# modulator_r1.net
KiCad netlist of a schematic drawn in EAGLE
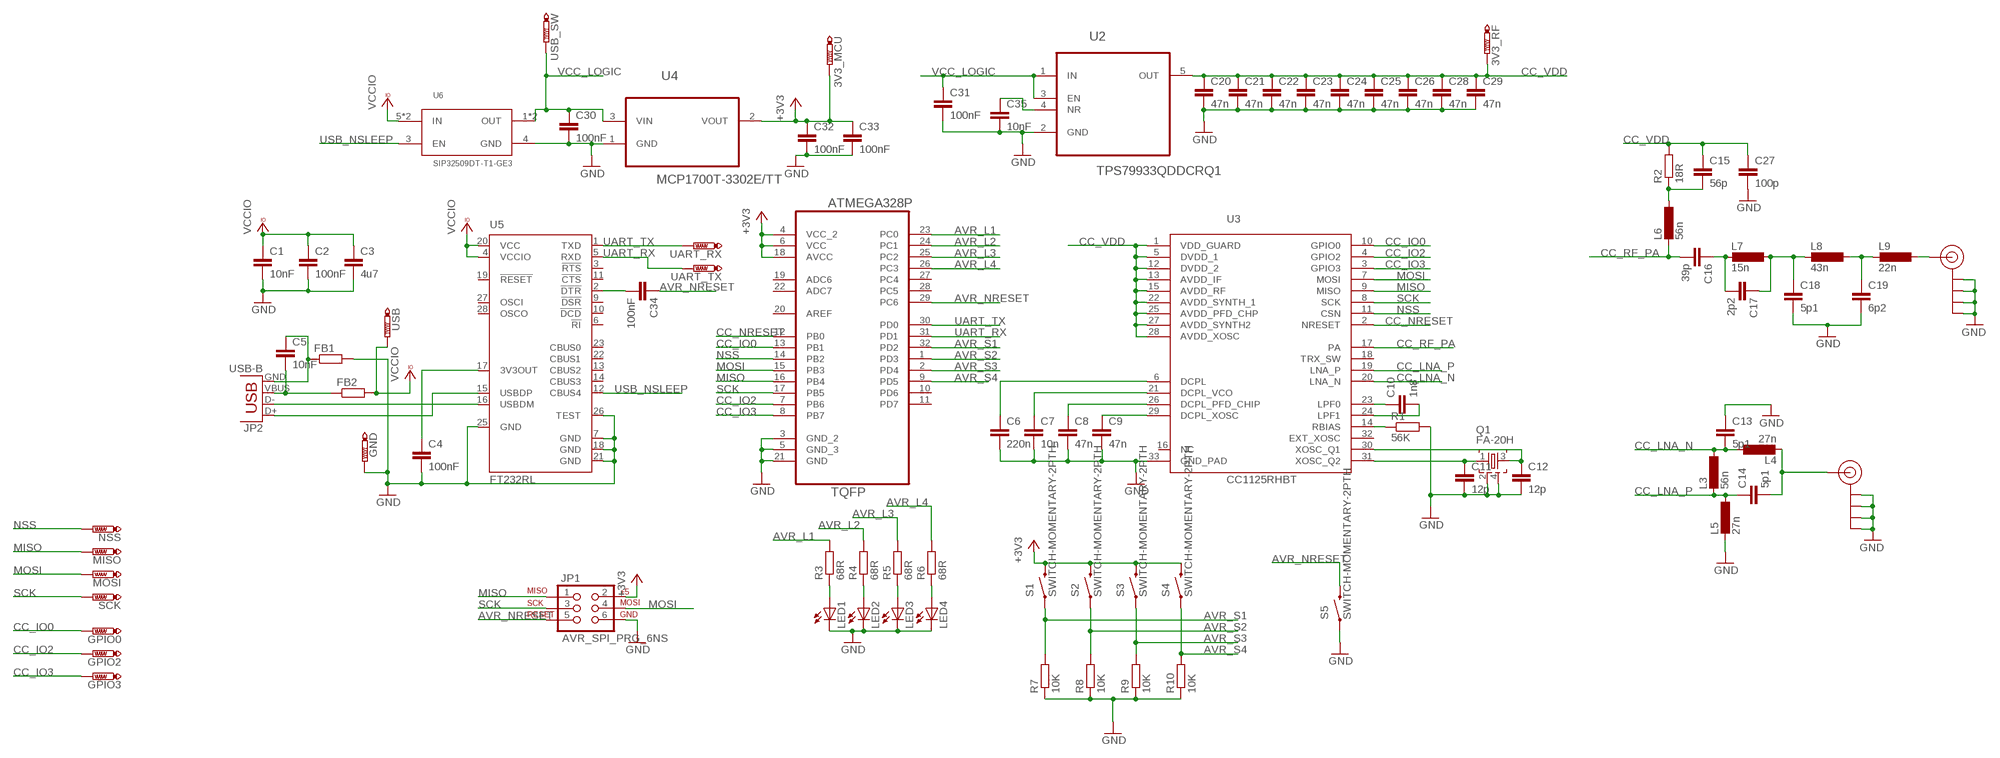
[diagram p0: schematic, sheet 1]

(export (version "E")
  (design (tool "Eeschema 10.0.6"))
  (components
    (comp (ref "3V3_MCU")
      (value "PTR1B2,54")
      (footprint "eagle-import:B2,54")
      (libsource (lib "eagle-import") (part "PTR1B2,54"))
    )
    (comp (ref "3V3_RF")
      (value "PTR1B2,54")
      (footprint "eagle-import:B2,54")
      (libsource (lib "eagle-import") (part "PTR1B2,54"))
    )
    (comp (ref "C1")
      (value "10nF")
      (footprint "eagle-import:C0603")
      (libsource (lib "eagle-import") (part "C-EUC0603"))
    )
    (comp (ref "C2")
      (value "100nF")
      (footprint "eagle-import:C0603")
      (libsource (lib "eagle-import") (part "C-EUC0603"))
    )
    (comp (ref "C3")
      (value "4u7")
      (footprint "eagle-import:C0603")
      (libsource (lib "eagle-import") (part "C-EUC0603"))
    )
    (comp (ref "C4")
      (value "100nF")
      (footprint "eagle-import:C0603")
      (libsource (lib "eagle-import") (part "C-EUC0603"))
    )
    (comp (ref "C5")
      (value "10nF")
      (footprint "eagle-import:C0603")
      (libsource (lib "eagle-import") (part "C-EUC0603"))
    )
    (comp (ref "C6")
      (value "220n")
      (footprint "eagle-import:C0402")
      (libsource (lib "eagle-import") (part "C-EUC0402"))
    )
    (comp (ref "C7")
      (value "10n")
      (footprint "eagle-import:C0402")
      (libsource (lib "eagle-import") (part "C-EUC0402"))
    )
    (comp (ref "C8")
      (value "47n")
      (footprint "eagle-import:C0402")
      (libsource (lib "eagle-import") (part "C-EUC0402"))
    )
    (comp (ref "C9")
      (value "47n")
      (footprint "eagle-import:C0402")
      (libsource (lib "eagle-import") (part "C-EUC0402"))
    )
    (comp (ref "C10")
      (value "1n8")
      (footprint "eagle-import:C0402")
      (libsource (lib "eagle-import") (part "C-EUC0402"))
    )
    (comp (ref "C11")
      (value "12p")
      (footprint "eagle-import:C0402")
      (libsource (lib "eagle-import") (part "C-EUC0402"))
    )
    (comp (ref "C12")
      (value "12p")
      (footprint "eagle-import:C0402")
      (libsource (lib "eagle-import") (part "C-EUC0402"))
    )
    (comp (ref "C13")
      (value "5p1")
      (footprint "eagle-import:C0402")
      (libsource (lib "eagle-import") (part "C-EUC0402"))
    )
    (comp (ref "C14")
      (value "5p1")
      (footprint "eagle-import:C0402")
      (libsource (lib "eagle-import") (part "C-EUC0402"))
    )
    (comp (ref "C15")
      (value "56p")
      (footprint "eagle-import:C0402")
      (libsource (lib "eagle-import") (part "C-EUC0402"))
    )
    (comp (ref "C16")
      (value "39p")
      (footprint "eagle-import:C0402")
      (libsource (lib "eagle-import") (part "C-EUC0402"))
    )
    (comp (ref "C17")
      (value "2p2")
      (footprint "eagle-import:C0402")
      (libsource (lib "eagle-import") (part "C-EUC0402"))
    )
    (comp (ref "C18")
      (value "5p1")
      (footprint "eagle-import:C0402")
      (libsource (lib "eagle-import") (part "C-EUC0402"))
    )
    (comp (ref "C19")
      (value "6p2")
      (footprint "eagle-import:C0402")
      (libsource (lib "eagle-import") (part "C-EUC0402"))
    )
    (comp (ref "C20")
      (value "47n")
      (footprint "eagle-import:C0402")
      (libsource (lib "eagle-import") (part "C-EUC0402"))
    )
    (comp (ref "C21")
      (value "47n")
      (footprint "eagle-import:C0402")
      (libsource (lib "eagle-import") (part "C-EUC0402"))
    )
    (comp (ref "C22")
      (value "47n")
      (footprint "eagle-import:C0402")
      (libsource (lib "eagle-import") (part "C-EUC0402"))
    )
    (comp (ref "C23")
      (value "47n")
      (footprint "eagle-import:C0402")
      (libsource (lib "eagle-import") (part "C-EUC0402"))
    )
    (comp (ref "C24")
      (value "47n")
      (footprint "eagle-import:C0402")
      (libsource (lib "eagle-import") (part "C-EUC0402"))
    )
    (comp (ref "C25")
      (value "47n")
      (footprint "eagle-import:C0402")
      (libsource (lib "eagle-import") (part "C-EUC0402"))
    )
    (comp (ref "C26")
      (value "47n")
      (footprint "eagle-import:C0402")
      (libsource (lib "eagle-import") (part "C-EUC0402"))
    )
    (comp (ref "C27")
      (value "100p")
      (footprint "eagle-import:C0402")
      (libsource (lib "eagle-import") (part "C-EUC0402"))
    )
    (comp (ref "C28")
      (value "47n")
      (footprint "eagle-import:C0402")
      (libsource (lib "eagle-import") (part "C-EUC0402"))
    )
    (comp (ref "C29")
      (value "47n")
      (footprint "eagle-import:C0402")
      (libsource (lib "eagle-import") (part "C-EUC0402"))
    )
    (comp (ref "C30")
      (value "100nF")
      (footprint "eagle-import:C0603")
      (libsource (lib "eagle-import") (part "C-EUC0603"))
    )
    (comp (ref "C31")
      (value "100nF")
      (footprint "eagle-import:C0603")
      (libsource (lib "eagle-import") (part "C-EUC0603"))
    )
    (comp (ref "C32")
      (value "100nF")
      (footprint "eagle-import:C0603")
      (libsource (lib "eagle-import") (part "C-EUC0603"))
    )
    (comp (ref "C33")
      (value "100nF")
      (footprint "eagle-import:C0603")
      (libsource (lib "eagle-import") (part "C-EUC0603"))
    )
    (comp (ref "C34")
      (value "100nF")
      (footprint "eagle-import:C0603")
      (libsource (lib "eagle-import") (part "C-EUC0603"))
    )
    (comp (ref "C35")
      (value "10nF")
      (footprint "eagle-import:C0603")
      (libsource (lib "eagle-import") (part "C-EUC0603"))
    )
    (comp (ref "FB1")
      (value "R-EU_R0603")
      (footprint "eagle-import:R0603")
      (libsource (lib "eagle-import") (part "R-EU_R0603"))
    )
    (comp (ref "FB2")
      (value "R-EU_R0603")
      (footprint "eagle-import:R0603")
      (libsource (lib "eagle-import") (part "R-EU_R0603"))
    )
    (comp (ref "GND")
      (value "PTR1B2,54")
      (footprint "eagle-import:B2,54")
      (libsource (lib "eagle-import") (part "PTR1B2,54"))
    )
    (comp (ref "GPIO0")
      (value "PTR1B1,27")
      (footprint "eagle-import:B1,27")
      (libsource (lib "eagle-import") (part "PTR1B1,27"))
    )
    (comp (ref "GPIO2")
      (value "PTR1B1,27")
      (footprint "eagle-import:B1,27")
      (libsource (lib "eagle-import") (part "PTR1B1,27"))
    )
    (comp (ref "GPIO3")
      (value "PTR1B1,27")
      (footprint "eagle-import:B1,27")
      (libsource (lib "eagle-import") (part "PTR1B1,27"))
    )
    (comp (ref "J$1")
      (value "SMA_EDGE")
      (footprint "eagle-import:SMA-EDGE")
      (libsource (lib "eagle-import") (part "SMA_EDGE"))
    )
    (comp (ref "J$2")
      (value "SMA_EDGE")
      (footprint "eagle-import:SMA-EDGE")
      (libsource (lib "eagle-import") (part "SMA_EDGE"))
    )
    (comp (ref "JP1")
      (value "AVR_SPI_PRG_6NS")
      (footprint "eagle-import:2X3-NS")
      (libsource (lib "eagle-import") (part "AVR_SPI_PRG_6NS"))
    )
    (comp (ref "JP2")
      (value "USB-B")
      (footprint "eagle-import:USB-B-PTH")
      (libsource (lib "eagle-import") (part "USBPTH"))
    )
    (comp (ref "L3")
      (value "56n")
      (footprint "eagle-import:R0402")
      (libsource (lib "eagle-import") (part "L-EUL0402"))
    )
    (comp (ref "L4")
      (value "27n")
      (footprint "eagle-import:R0402")
      (libsource (lib "eagle-import") (part "L-EUL0402"))
    )
    (comp (ref "L5")
      (value "27n")
      (footprint "eagle-import:R0402")
      (libsource (lib "eagle-import") (part "L-EUL0402"))
    )
    (comp (ref "L6")
      (value "56n")
      (footprint "eagle-import:R0402")
      (libsource (lib "eagle-import") (part "L-EUL0402"))
    )
    (comp (ref "L7")
      (value "15n")
      (footprint "eagle-import:R0402")
      (libsource (lib "eagle-import") (part "L-EUL0402"))
    )
    (comp (ref "L8")
      (value "43n")
      (footprint "eagle-import:R0402")
      (libsource (lib "eagle-import") (part "L-EUL0402"))
    )
    (comp (ref "L9")
      (value "22n")
      (footprint "eagle-import:R0402")
      (libsource (lib "eagle-import") (part "L-EUL0402"))
    )
    (comp (ref "LED1")
      (value "LEDCHIPLED_1206")
      (footprint "eagle-import:CHIPLED_1206")
      (libsource (lib "eagle-import") (part "LEDCHIPLED_1206"))
    )
    (comp (ref "LED2")
      (value "LEDCHIPLED_1206")
      (footprint "eagle-import:CHIPLED_1206")
      (libsource (lib "eagle-import") (part "LEDCHIPLED_1206"))
    )
    (comp (ref "LED3")
      (value "LEDCHIPLED_1206")
      (footprint "eagle-import:CHIPLED_1206")
      (libsource (lib "eagle-import") (part "LEDCHIPLED_1206"))
    )
    (comp (ref "LED4")
      (value "LEDCHIPLED_1206")
      (footprint "eagle-import:CHIPLED_1206")
      (libsource (lib "eagle-import") (part "LEDCHIPLED_1206"))
    )
    (comp (ref "MISO")
      (value "PTR1B1,27")
      (footprint "eagle-import:B1,27")
      (libsource (lib "eagle-import") (part "PTR1B1,27"))
    )
    (comp (ref "MOSI")
      (value "PTR1B1,27")
      (footprint "eagle-import:B1,27")
      (libsource (lib "eagle-import") (part "PTR1B1,27"))
    )
    (comp (ref "NSS")
      (value "PTR1B1,27")
      (footprint "eagle-import:B1,27")
      (libsource (lib "eagle-import") (part "PTR1B1,27"))
    )
    (comp (ref "Q1")
      (value "FA-20H")
      (footprint "eagle-import:FA-20H")
      (libsource (lib "eagle-import") (part "FA-20H"))
    )
    (comp (ref "R1")
      (value "56K")
      (footprint "eagle-import:R0402")
      (libsource (lib "eagle-import") (part "R-EU_R0402"))
    )
    (comp (ref "R2")
      (value "18R")
      (footprint "eagle-import:R0402")
      (libsource (lib "eagle-import") (part "R-EU_R0402"))
    )
    (comp (ref "R3")
      (value "68R")
      (footprint "eagle-import:R0603")
      (libsource (lib "eagle-import") (part "R-EU_R0603"))
    )
    (comp (ref "R4")
      (value "68R")
      (footprint "eagle-import:R0603")
      (libsource (lib "eagle-import") (part "R-EU_R0603"))
    )
    (comp (ref "R5")
      (value "68R")
      (footprint "eagle-import:R0603")
      (libsource (lib "eagle-import") (part "R-EU_R0603"))
    )
    (comp (ref "R6")
      (value "68R")
      (footprint "eagle-import:R0603")
      (libsource (lib "eagle-import") (part "R-EU_R0603"))
    )
    (comp (ref "R7")
      (value "10K")
      (footprint "eagle-import:R0603")
      (libsource (lib "eagle-import") (part "R-EU_R0603"))
    )
    (comp (ref "R8")
      (value "10K")
      (footprint "eagle-import:R0603")
      (libsource (lib "eagle-import") (part "R-EU_R0603"))
    )
    (comp (ref "R9")
      (value "10K")
      (footprint "eagle-import:R0603")
      (libsource (lib "eagle-import") (part "R-EU_R0603"))
    )
    (comp (ref "R10")
      (value "10K")
      (footprint "eagle-import:R0603")
      (libsource (lib "eagle-import") (part "R-EU_R0603"))
    )
    (comp (ref "S1")
      (value "SWITCH-MOMENTARY-2PTH")
      (footprint "eagle-import:TACTILE-PTH")
      (libsource (lib "eagle-import") (part "SWITCH-MOMENTARY-2PTH"))
    )
    (comp (ref "S2")
      (value "SWITCH-MOMENTARY-2PTH")
      (footprint "eagle-import:TACTILE-PTH")
      (libsource (lib "eagle-import") (part "SWITCH-MOMENTARY-2PTH"))
    )
    (comp (ref "S3")
      (value "SWITCH-MOMENTARY-2PTH")
      (footprint "eagle-import:TACTILE-PTH")
      (libsource (lib "eagle-import") (part "SWITCH-MOMENTARY-2PTH"))
    )
    (comp (ref "S4")
      (value "SWITCH-MOMENTARY-2PTH")
      (footprint "eagle-import:TACTILE-PTH")
      (libsource (lib "eagle-import") (part "SWITCH-MOMENTARY-2PTH"))
    )
    (comp (ref "S5")
      (value "SWITCH-MOMENTARY-2PTH")
      (footprint "eagle-import:TACTILE-PTH")
      (libsource (lib "eagle-import") (part "SWITCH-MOMENTARY-2PTH"))
    )
    (comp (ref "SCK")
      (value "PTR1B1,27")
      (footprint "eagle-import:B1,27")
      (libsource (lib "eagle-import") (part "PTR1B1,27"))
    )
    (comp (ref "U1")
      (value "ATMEGA328P-AU")
      (footprint "eagle-import:QFP80P900X900X120-32N")
      (libsource (lib "eagle-import") (part "ATMEGA328P-AU"))
    )
    (comp (ref "U2")
      (value "TPS79933QDDCRQ1")
      (footprint "eagle-import:SOT95P280X110-5N")
      (libsource (lib "eagle-import") (part "TPS79933QDDCRQ1"))
    )
    (comp (ref "U3")
      (value "CC1125RHBT")
      (footprint "eagle-import:QFN50P500X500X100-32N")
      (libsource (lib "eagle-import") (part "CC1125RHBT"))
    )
    (comp (ref "U4")
      (value "MCP1700T-3302E/TT")
      (footprint "eagle-import:SOT95P237X112-3N")
      (libsource (lib "eagle-import") (part "MCP1700T-3302E/TT"))
    )
    (comp (ref "U5")
      (value "FT232RL")
      (footprint "eagle-import:SSOP28")
      (libsource (lib "eagle-import") (part "FT232RL"))
    )
    (comp (ref "U6")
      (value "SIP32509DT-T1-GE3")
      (footprint "eagle-import:SOT23-6")
      (libsource (lib "eagle-import") (part "SIP32509DT-T1-GE3"))
    )
    (comp (ref "UART_RX")
      (value "PTR1B1,27")
      (footprint "eagle-import:B1,27")
      (libsource (lib "eagle-import") (part "PTR1B1,27"))
    )
    (comp (ref "UART_TX")
      (value "PTR1B1,27")
      (footprint "eagle-import:B1,27")
      (libsource (lib "eagle-import") (part "PTR1B1,27"))
    )
    (comp (ref "USB")
      (value "PTR1B2,54")
      (footprint "eagle-import:B2,54")
      (libsource (lib "eagle-import") (part "PTR1B2,54"))
    )
    (comp (ref "USB_SW")
      (value "PTR1B2,54")
      (footprint "eagle-import:B2,54")
      (libsource (lib "eagle-import") (part "PTR1B2,54"))
    )
  )
  (nets
    (net (code "1") (name "+3V3") (class "Default")
      (node (ref "3V3_MCU") (pin "TP") (pinfunction "TP_TP") (pintype "input"))
      (node (ref "C32") (pin "1") (pinfunction "1_1") (pintype "passive"))
      (node (ref "C33") (pin "1") (pinfunction "1_1") (pintype "passive"))
      (node (ref "JP1") (pin "2") (pinfunction "2_2") (pintype "passive"))
      (node (ref "S1") (pin "3") (pinfunction "2_3") (pintype "passive"))
      (node (ref "S2") (pin "3") (pinfunction "2_3") (pintype "passive"))
      (node (ref "S3") (pin "3") (pinfunction "2_3") (pintype "passive"))
      (node (ref "S4") (pin "3") (pinfunction "2_3") (pintype "passive"))
      (node (ref "U1") (pin "18") (pinfunction "AVCC_18") (pintype "power_in"))
      (node (ref "U1") (pin "4") (pinfunction "VCC_2_4") (pintype "power_in"))
      (node (ref "U1") (pin "6") (pinfunction "VCC_6") (pintype "power_in"))
      (node (ref "U4") (pin "2") (pinfunction "VOUT_2") (pintype "output"))
    )
    (net (code "2") (name "/AVR_L1") (class "Default")
      (node (ref "R3") (pin "2") (pinfunction "2_2") (pintype "passive"))
      (node (ref "U1") (pin "23") (pinfunction "PC0_23") (pintype "bidirectional"))
    )
    (net (code "3") (name "/AVR_L2") (class "Default")
      (node (ref "R4") (pin "2") (pinfunction "2_2") (pintype "passive"))
      (node (ref "U1") (pin "24") (pinfunction "PC1_24") (pintype "bidirectional"))
    )
    (net (code "4") (name "/AVR_L3") (class "Default")
      (node (ref "R5") (pin "2") (pinfunction "2_2") (pintype "passive"))
      (node (ref "U1") (pin "25") (pinfunction "PC2_25") (pintype "bidirectional"))
    )
    (net (code "5") (name "/AVR_L4") (class "Default")
      (node (ref "R6") (pin "2") (pinfunction "2_2") (pintype "passive"))
      (node (ref "U1") (pin "26") (pinfunction "PC3_26") (pintype "bidirectional"))
    )
    (net (code "6") (name "/AVR_NRESET") (class "Default")
      (node (ref "C34") (pin "1") (pinfunction "1_1") (pintype "passive"))
      (node (ref "JP1") (pin "5") (pinfunction "5_5") (pintype "passive"))
      (node (ref "S5") (pin "3") (pinfunction "2_3") (pintype "passive"))
      (node (ref "U1") (pin "29") (pinfunction "PC6_29") (pintype "bidirectional"))
    )
    (net (code "7") (name "/AVR_S1") (class "Default")
      (node (ref "R7") (pin "2") (pinfunction "2_2") (pintype "passive"))
      (node (ref "S1") (pin "1") (pinfunction "1_1") (pintype "passive"))
      (node (ref "U1") (pin "32") (pinfunction "PD2_32") (pintype "bidirectional"))
    )
    (net (code "8") (name "/AVR_S2") (class "Default")
      (node (ref "R8") (pin "2") (pinfunction "2_2") (pintype "passive"))
      (node (ref "S2") (pin "1") (pinfunction "1_1") (pintype "passive"))
      (node (ref "U1") (pin "1") (pinfunction "PD3_1") (pintype "bidirectional"))
    )
    (net (code "9") (name "/AVR_S3") (class "Default")
      (node (ref "R9") (pin "2") (pinfunction "2_2") (pintype "passive"))
      (node (ref "S3") (pin "1") (pinfunction "1_1") (pintype "passive"))
      (node (ref "U1") (pin "2") (pinfunction "PD4_2") (pintype "bidirectional"))
    )
    (net (code "10") (name "/AVR_S4") (class "Default")
      (node (ref "R10") (pin "2") (pinfunction "2_2") (pintype "passive"))
      (node (ref "S4") (pin "1") (pinfunction "1_1") (pintype "passive"))
      (node (ref "U1") (pin "9") (pinfunction "PD5_9") (pintype "bidirectional"))
    )
    (net (code "11") (name "/CC_IO0") (class "Default")
      (node (ref "GPIO0") (pin "TP") (pinfunction "TP_TP") (pintype "input"))
      (node (ref "U1") (pin "13") (pinfunction "PB1_13") (pintype "bidirectional"))
      (node (ref "U3") (pin "10") (pinfunction "GPIO0_10") (pintype "bidirectional"))
    )
    (net (code "12") (name "/CC_IO2") (class "Default")
      (node (ref "GPIO2") (pin "TP") (pinfunction "TP_TP") (pintype "input"))
      (node (ref "U1") (pin "7") (pinfunction "PB6_7") (pintype "bidirectional"))
      (node (ref "U3") (pin "4") (pinfunction "GPIO2_4") (pintype "bidirectional"))
    )
    (net (code "13") (name "/CC_IO3") (class "Default")
      (node (ref "GPIO3") (pin "TP") (pinfunction "TP_TP") (pintype "input"))
      (node (ref "U1") (pin "8") (pinfunction "PB7_8") (pintype "bidirectional"))
      (node (ref "U3") (pin "3") (pinfunction "GPIO3_3") (pintype "bidirectional"))
    )
    (net (code "14") (name "/CC_LNA_N") (class "Default")
      (node (ref "C13") (pin "2") (pinfunction "2_2") (pintype "passive"))
      (node (ref "L3") (pin "1") (pinfunction "1_1") (pintype "passive"))
      (node (ref "L4") (pin "1") (pinfunction "1_1") (pintype "passive"))
      (node (ref "U3") (pin "20") (pinfunction "LNA_N_20") (pintype "bidirectional"))
    )
    (net (code "15") (name "/CC_LNA_P") (class "Default")
      (node (ref "C14") (pin "1") (pinfunction "1_1") (pintype "passive"))
      (node (ref "L3") (pin "2") (pinfunction "2_2") (pintype "passive"))
      (node (ref "L5") (pin "1") (pinfunction "1_1") (pintype "passive"))
      (node (ref "U3") (pin "19") (pinfunction "LNA_P_19") (pintype "bidirectional"))
    )
    (net (code "16") (name "/CC_NRESET") (class "Default")
      (node (ref "U1") (pin "12") (pinfunction "PB0_12") (pintype "bidirectional"))
      (node (ref "U3") (pin "2") (pinfunction "NRESET_2") (pintype "bidirectional"))
    )
    (net (code "17") (name "/CC_RF_PA") (class "Default")
      (node (ref "C16") (pin "2") (pinfunction "2_2") (pintype "passive"))
      (node (ref "L6") (pin "2") (pinfunction "2_2") (pintype "passive"))
      (node (ref "U3") (pin "17") (pinfunction "PA_17") (pintype "bidirectional"))
    )
    (net (code "18") (name "/CC_VDD") (class "Default")
      (node (ref "3V3_RF") (pin "TP") (pinfunction "TP_TP") (pintype "input"))
      (node (ref "C15") (pin "1") (pinfunction "1_1") (pintype "passive"))
      (node (ref "C20") (pin "1") (pinfunction "1_1") (pintype "passive"))
      (node (ref "C21") (pin "1") (pinfunction "1_1") (pintype "passive"))
      (node (ref "C22") (pin "1") (pinfunction "1_1") (pintype "passive"))
      (node (ref "C23") (pin "1") (pinfunction "1_1") (pintype "passive"))
      (node (ref "C24") (pin "1") (pinfunction "1_1") (pintype "passive"))
      (node (ref "C25") (pin "1") (pinfunction "1_1") (pintype "passive"))
      (node (ref "C26") (pin "1") (pinfunction "1_1") (pintype "passive"))
      (node (ref "C27") (pin "1") (pinfunction "1_1") (pintype "passive"))
      (node (ref "C28") (pin "1") (pinfunction "1_1") (pintype "passive"))
      (node (ref "C29") (pin "1") (pinfunction "1_1") (pintype "passive"))
      (node (ref "R2") (pin "2") (pinfunction "2_2") (pintype "passive"))
      (node (ref "U2") (pin "5") (pinfunction "OUT_5") (pintype "output"))
      (node (ref "U3") (pin "1") (pinfunction "VDD_GUARD_1") (pintype "bidirectional"))
      (node (ref "U3") (pin "12") (pinfunction "DVDD_2_12") (pintype "bidirectional"))
      (node (ref "U3") (pin "13") (pinfunction "AVDD_IF_13") (pintype "bidirectional"))
      (node (ref "U3") (pin "15") (pinfunction "AVDD_RF_15") (pintype "bidirectional"))
      (node (ref "U3") (pin "22") (pinfunction "AVDD_SYNTH_1_22") (pintype "bidirectional"))
      (node (ref "U3") (pin "25") (pinfunction "AVDD_PFD_CHP_25") (pintype "bidirectional"))
      (node (ref "U3") (pin "27") (pinfunction "AVDD_SYNTH2_27") (pintype "bidirectional"))
      (node (ref "U3") (pin "28") (pinfunction "AVDD_XOSC_28") (pintype "bidirectional"))
      (node (ref "U3") (pin "5") (pinfunction "DVDD_1_5") (pintype "bidirectional"))
    )
    (net (code "19") (name "/MISO") (class "Default")
      (node (ref "JP1") (pin "1") (pinfunction "1_1") (pintype "passive"))
      (node (ref "MISO") (pin "TP") (pinfunction "TP_TP") (pintype "input"))
      (node (ref "U1") (pin "16") (pinfunction "PB4_16") (pintype "bidirectional"))
      (node (ref "U3") (pin "9") (pinfunction "MISO_9") (pintype "bidirectional"))
    )
    (net (code "20") (name "/MOSI") (class "Default")
      (node (ref "JP1") (pin "4") (pinfunction "4_4") (pintype "passive"))
      (node (ref "MOSI") (pin "TP") (pinfunction "TP_TP") (pintype "input"))
      (node (ref "U1") (pin "15") (pinfunction "PB3_15") (pintype "bidirectional"))
      (node (ref "U3") (pin "7") (pinfunction "MOSI_7") (pintype "bidirectional"))
    )
    (net (code "21") (name "/NSS") (class "Default")
      (node (ref "NSS") (pin "TP") (pinfunction "TP_TP") (pintype "input"))
      (node (ref "U1") (pin "14") (pinfunction "PB2_14") (pintype "bidirectional"))
      (node (ref "U3") (pin "11") (pinfunction "CSN_11") (pintype "bidirectional"))
    )
    (net (code "22") (name "/SCK") (class "Default")
      (node (ref "JP1") (pin "3") (pinfunction "3_3") (pintype "passive"))
      (node (ref "SCK") (pin "TP") (pinfunction "TP_TP") (pintype "input"))
      (node (ref "U1") (pin "17") (pinfunction "PB5_17") (pintype "bidirectional"))
      (node (ref "U3") (pin "8") (pinfunction "SCK_8") (pintype "bidirectional"))
    )
    (net (code "23") (name "/UART_RX") (class "Default")
      (node (ref "U1") (pin "31") (pinfunction "PD1_31") (pintype "bidirectional"))
      (node (ref "U5") (pin "5") (pinfunction "RXD_5") (pintype "input"))
      (node (ref "UART_TX") (pin "TP") (pinfunction "TP_TP") (pintype "input"))
    )
    (net (code "24") (name "/UART_TX") (class "Default")
      (node (ref "U1") (pin "30") (pinfunction "PD0_30") (pintype "bidirectional"))
      (node (ref "U5") (pin "1") (pinfunction "TXD_1") (pintype "output"))
      (node (ref "UART_RX") (pin "TP") (pinfunction "TP_TP") (pintype "input"))
    )
    (net (code "25") (name "/USB_NSLEEP") (class "Default")
      (node (ref "U5") (pin "12") (pinfunction "CBUS4_12") (pintype "bidirectional"))
      (node (ref "U6") (pin "3") (pinfunction "EN_3") (pintype "bidirectional"))
    )
    (net (code "26") (name "/VCC_LOGIC") (class "Default")
      (node (ref "C30") (pin "1") (pinfunction "1_1") (pintype "passive"))
      (node (ref "C31") (pin "1") (pinfunction "1_1") (pintype "passive"))
      (node (ref "U2") (pin "1") (pinfunction "IN_1") (pintype "power_in"))
      (node (ref "U2") (pin "3") (pinfunction "EN_3") (pintype "input"))
      (node (ref "U4") (pin "3") (pinfunction "VIN_3") (pintype "input"))
      (node (ref "U6") (pin "1") (pinfunction "OUT_1") (pintype "bidirectional"))
      (node (ref "U6") (pin "2") (pinfunction "OUT_2") (pintype "bidirectional"))
      (node (ref "USB_SW") (pin "TP") (pinfunction "TP_TP") (pintype "input"))
    )
    (net (code "27") (name "GND") (class "Default")
      (node (ref "C1") (pin "2") (pinfunction "2_2") (pintype "passive"))
      (node (ref "C11") (pin "2") (pinfunction "2_2") (pintype "passive"))
      (node (ref "C12") (pin "2") (pinfunction "2_2") (pintype "passive"))
      (node (ref "C13") (pin "1") (pinfunction "1_1") (pintype "passive"))
      (node (ref "C18") (pin "2") (pinfunction "2_2") (pintype "passive"))
      (node (ref "C19") (pin "2") (pinfunction "2_2") (pintype "passive"))
      (node (ref "C2") (pin "2") (pinfunction "2_2") (pintype "passive"))
      (node (ref "C20") (pin "2") (pinfunction "2_2") (pintype "passive"))
      (node (ref "C21") (pin "2") (pinfunction "2_2") (pintype "passive"))
      (node (ref "C22") (pin "2") (pinfunction "2_2") (pintype "passive"))
      (node (ref "C23") (pin "2") (pinfunction "2_2") (pintype "passive"))
      (node (ref "C24") (pin "2") (pinfunction "2_2") (pintype "passive"))
      (node (ref "C25") (pin "2") (pinfunction "2_2") (pintype "passive"))
      (node (ref "C26") (pin "2") (pinfunction "2_2") (pintype "passive"))
      (node (ref "C27") (pin "2") (pinfunction "2_2") (pintype "passive"))
      (node (ref "C28") (pin "2") (pinfunction "2_2") (pintype "passive"))
      (node (ref "C29") (pin "2") (pinfunction "2_2") (pintype "passive"))
      (node (ref "C3") (pin "2") (pinfunction "2_2") (pintype "passive"))
      (node (ref "C30") (pin "2") (pinfunction "2_2") (pintype "passive"))
      (node (ref "C31") (pin "2") (pinfunction "2_2") (pintype "passive"))
      (node (ref "C32") (pin "2") (pinfunction "2_2") (pintype "passive"))
      (node (ref "C33") (pin "2") (pinfunction "2_2") (pintype "passive"))
      (node (ref "C35") (pin "2") (pinfunction "2_2") (pintype "passive"))
      (node (ref "C4") (pin "2") (pinfunction "2_2") (pintype "passive"))
      (node (ref "C6") (pin "2") (pinfunction "2_2") (pintype "passive"))
      (node (ref "C7") (pin "2") (pinfunction "2_2") (pintype "passive"))
      (node (ref "C8") (pin "2") (pinfunction "2_2") (pintype "passive"))
      (node (ref "C9") (pin "2") (pinfunction "2_2") (pintype "passive"))
      (node (ref "FB1") (pin "2") (pinfunction "2_2") (pintype "passive"))
      (node (ref "GND") (pin "TP") (pinfunction "TP_TP") (pintype "input"))
      (node (ref "J$1") (pin "GND@0") (pinfunction "GND_GND@0") (pintype "bidirectional"))
      (node (ref "J$1") (pin "GND@1") (pinfunction "GND_GND@1") (pintype "bidirectional"))
      (node (ref "J$1") (pin "GND@2") (pinfunction "GND_GND@2") (pintype "bidirectional"))
      (node (ref "J$1") (pin "GND@3") (pinfunction "GND_GND@3") (pintype "bidirectional"))
      (node (ref "J$2") (pin "GND@0") (pinfunction "GND_GND@0") (pintype "bidirectional"))
      (node (ref "J$2") (pin "GND@1") (pinfunction "GND_GND@1") (pintype "bidirectional"))
      (node (ref "J$2") (pin "GND@2") (pinfunction "GND_GND@2") (pintype "bidirectional"))
      (node (ref "J$2") (pin "GND@3") (pinfunction "GND_GND@3") (pintype "bidirectional"))
      (node (ref "JP1") (pin "6") (pinfunction "6_6") (pintype "passive"))
      (node (ref "L5") (pin "2") (pinfunction "2_2") (pintype "passive"))
      (node (ref "LED1") (pin "C") (pinfunction "C_C") (pintype "passive"))
      (node (ref "LED2") (pin "C") (pinfunction "C_C") (pintype "passive"))
      (node (ref "LED3") (pin "C") (pinfunction "C_C") (pintype "passive"))
      (node (ref "LED4") (pin "C") (pinfunction "C_C") (pintype "passive"))
      (node (ref "Q1") (pin "2") (pinfunction "2_2") (pintype "passive"))
      (node (ref "Q1") (pin "4") (pinfunction "4_4") (pintype "passive"))
      (node (ref "R1") (pin "2") (pinfunction "2_2") (pintype "passive"))
      (node (ref "R10") (pin "1") (pinfunction "1_1") (pintype "passive"))
      (node (ref "R7") (pin "1") (pinfunction "1_1") (pintype "passive"))
      (node (ref "R8") (pin "1") (pinfunction "1_1") (pintype "passive"))
      (node (ref "R9") (pin "1") (pinfunction "1_1") (pintype "passive"))
      (node (ref "S5") (pin "1") (pinfunction "1_1") (pintype "passive"))
      (node (ref "U1") (pin "21") (pinfunction "GND_21") (pintype "passive"))
      (node (ref "U1") (pin "3") (pinfunction "GND_2_3") (pintype "passive"))
      (node (ref "U1") (pin "5") (pinfunction "GND_3_5") (pintype "passive"))
      (node (ref "U2") (pin "2") (pinfunction "GND_2") (pintype "passive"))
      (node (ref "U3") (pin "33") (pinfunction "GND_PAD_33") (pintype "bidirectional"))
      (node (ref "U4") (pin "1") (pinfunction "GND_1") (pintype "passive"))
      (node (ref "U5") (pin "18") (pinfunction "GND_18") (pintype "power_in"))
      (node (ref "U5") (pin "21") (pinfunction "GND_21") (pintype "power_in"))
      (node (ref "U5") (pin "25") (pinfunction "GND_25") (pintype "power_in"))
      (node (ref "U5") (pin "26") (pinfunction "TEST_26") (pintype "input"))
      (node (ref "U5") (pin "7") (pinfunction "GND_7") (pintype "power_in"))
      (node (ref "U6") (pin "4") (pinfunction "GND_4") (pintype "bidirectional"))
    )
    (net (code "28") (name "Net-(C5-Pad1)") (class "Default")
      (node (ref "C5") (pin "1") (pinfunction "1_1") (pintype "passive"))
      (node (ref "FB1") (pin "1") (pinfunction "1_1") (pintype "passive"))
      (node (ref "JP2") (pin "GND") (pinfunction "GND_GND") (pintype "bidirectional"))
    )
    (net (code "29") (name "Net-(C5-Pad2)") (class "Default")
      (node (ref "C5") (pin "2") (pinfunction "2_2") (pintype "passive"))
      (node (ref "FB2") (pin "1") (pinfunction "1_1") (pintype "passive"))
      (node (ref "JP2") (pin "VBUS") (pinfunction "VBUS_VBUS") (pintype "bidirectional"))
    )
    (net (code "30") (name "Net-(C15-Pad2)") (class "Default")
      (node (ref "C15") (pin "2") (pinfunction "2_2") (pintype "passive"))
      (node (ref "L6") (pin "1") (pinfunction "1_1") (pintype "passive"))
      (node (ref "R2") (pin "1") (pinfunction "1_1") (pintype "passive"))
    )
    (net (code "31") (name "Net-(C16-Pad1)") (class "Default")
      (node (ref "C16") (pin "1") (pinfunction "1_1") (pintype "passive"))
      (node (ref "C17") (pin "2") (pinfunction "2_2") (pintype "passive"))
      (node (ref "L7") (pin "2") (pinfunction "2_2") (pintype "passive"))
    )
    (net (code "32") (name "Net-(C17-Pad1)") (class "Default")
      (node (ref "C17") (pin "1") (pinfunction "1_1") (pintype "passive"))
      (node (ref "C18") (pin "1") (pinfunction "1_1") (pintype "passive"))
      (node (ref "L7") (pin "1") (pinfunction "1_1") (pintype "passive"))
      (node (ref "L8") (pin "2") (pinfunction "2_2") (pintype "passive"))
    )
    (net (code "33") (name "Net-(C19-Pad1)") (class "Default")
      (node (ref "C19") (pin "1") (pinfunction "1_1") (pintype "passive"))
      (node (ref "L8") (pin "1") (pinfunction "1_1") (pintype "passive"))
      (node (ref "L9") (pin "2") (pinfunction "2_2") (pintype "passive"))
    )
    (net (code "34") (name "Net-(J$1-SIGNAL)") (class "Default")
      (node (ref "C14") (pin "2") (pinfunction "2_2") (pintype "passive"))
      (node (ref "J$1") (pin "SIG") (pinfunction "SIGNAL_SIG") (pintype "bidirectional"))
      (node (ref "L4") (pin "2") (pinfunction "2_2") (pintype "passive"))
    )
    (net (code "35") (name "Net-(J$2-SIGNAL)") (class "Default")
      (node (ref "J$2") (pin "SIG") (pinfunction "SIGNAL_SIG") (pintype "bidirectional"))
      (node (ref "L9") (pin "1") (pinfunction "1_1") (pintype "passive"))
    )
    (net (code "36") (name "Net-(LED1-PadA)") (class "Default")
      (node (ref "LED1") (pin "A") (pinfunction "A_A") (pintype "passive"))
      (node (ref "R3") (pin "1") (pinfunction "1_1") (pintype "passive"))
    )
    (net (code "37") (name "Net-(LED2-PadA)") (class "Default")
      (node (ref "LED2") (pin "A") (pinfunction "A_A") (pintype "passive"))
      (node (ref "R4") (pin "1") (pinfunction "1_1") (pintype "passive"))
    )
    (net (code "38") (name "Net-(LED3-PadA)") (class "Default")
      (node (ref "LED3") (pin "A") (pinfunction "A_A") (pintype "passive"))
      (node (ref "R5") (pin "1") (pinfunction "1_1") (pintype "passive"))
    )
    (net (code "39") (name "Net-(LED4-PadA)") (class "Default")
      (node (ref "LED4") (pin "A") (pinfunction "A_A") (pintype "passive"))
      (node (ref "R6") (pin "1") (pinfunction "1_1") (pintype "passive"))
    )
    (net (code "40") (name "Net-(U2-NR)") (class "Default")
      (node (ref "C35") (pin "1") (pinfunction "1_1") (pintype "passive"))
      (node (ref "U2") (pin "4") (pinfunction "NR_4") (pintype "input"))
    )
    (net (code "41") (name "Net-(U3-DCPL)") (class "Default")
      (node (ref "C6") (pin "1") (pinfunction "1_1") (pintype "passive"))
      (node (ref "U3") (pin "6") (pinfunction "DCPL_6") (pintype "bidirectional"))
    )
    (net (code "42") (name "Net-(U3-DCPL_PFD_CHIP)") (class "Default")
      (node (ref "C8") (pin "1") (pinfunction "1_1") (pintype "passive"))
      (node (ref "U3") (pin "26") (pinfunction "DCPL_PFD_CHIP_26") (pintype "bidirectional"))
    )
    (net (code "43") (name "Net-(U3-DCPL_VCO)") (class "Default")
      (node (ref "C7") (pin "1") (pinfunction "1_1") (pintype "passive"))
      (node (ref "U3") (pin "21") (pinfunction "DCPL_VCO_21") (pintype "bidirectional"))
    )
    (net (code "44") (name "Net-(U3-DCPL_XOSC)") (class "Default")
      (node (ref "C9") (pin "1") (pinfunction "1_1") (pintype "passive"))
      (node (ref "U3") (pin "29") (pinfunction "DCPL_XOSC_29") (pintype "bidirectional"))
    )
    (net (code "45") (name "Net-(U3-LPF0)") (class "Default")
      (node (ref "C10") (pin "1") (pinfunction "1_1") (pintype "passive"))
      (node (ref "U3") (pin "23") (pinfunction "LPF0_23") (pintype "bidirectional"))
    )
    (net (code "46") (name "Net-(U3-LPF1)") (class "Default")
      (node (ref "C10") (pin "2") (pinfunction "2_2") (pintype "passive"))
      (node (ref "U3") (pin "24") (pinfunction "LPF1_24") (pintype "bidirectional"))
    )
    (net (code "47") (name "Net-(U3-RBIAS)") (class "Default")
      (node (ref "R1") (pin "1") (pinfunction "1_1") (pintype "passive"))
      (node (ref "U3") (pin "14") (pinfunction "RBIAS_14") (pintype "bidirectional"))
    )
    (net (code "48") (name "Net-(U3-XOSC_Q1)") (class "Default")
      (node (ref "C12") (pin "1") (pinfunction "1_1") (pintype "passive"))
      (node (ref "Q1") (pin "3") (pinfunction "3_3") (pintype "passive"))
      (node (ref "U3") (pin "30") (pinfunction "XOSC_Q1_30") (pintype "bidirectional"))
    )
    (net (code "49") (name "Net-(U3-XOSC_Q2)") (class "Default")
      (node (ref "C11") (pin "1") (pinfunction "1_1") (pintype "passive"))
      (node (ref "Q1") (pin "1") (pinfunction "1_1") (pintype "passive"))
      (node (ref "U3") (pin "31") (pinfunction "XOSC_Q2_31") (pintype "bidirectional"))
    )
    (net (code "50") (name "Net-(U5-3V3OUT)") (class "Default")
      (node (ref "C4") (pin "1") (pinfunction "1_1") (pintype "passive"))
      (node (ref "U5") (pin "17") (pinfunction "3V3OUT_17") (pintype "output"))
    )
    (net (code "51") (name "Net-(U5-USBDM)") (class "Default")
      (node (ref "JP2") (pin "D-") (pinfunction "D-_D-") (pintype "bidirectional"))
      (node (ref "U5") (pin "16") (pinfunction "USBDM_16") (pintype "bidirectional"))
    )
    (net (code "52") (name "Net-(U5-USBDP)") (class "Default")
      (node (ref "JP2") (pin "D+") (pinfunction "D+_D+") (pintype "bidirectional"))
      (node (ref "U5") (pin "15") (pinfunction "USBDP_15") (pintype "bidirectional"))
    )
    (net (code "53") (name "Net-(U5-~{DTR})") (class "Default")
      (node (ref "C34") (pin "2") (pinfunction "2_2") (pintype "passive"))
      (node (ref "U5") (pin "2") (pinfunction "~{DTR}_2") (pintype "output"))
    )
    (net (code "54") (name "VCCIO") (class "Default")
      (node (ref "C1") (pin "1") (pinfunction "1_1") (pintype "passive"))
      (node (ref "C2") (pin "1") (pinfunction "1_1") (pintype "passive"))
      (node (ref "C3") (pin "1") (pinfunction "1_1") (pintype "passive"))
      (node (ref "FB2") (pin "2") (pinfunction "2_2") (pintype "passive"))
      (node (ref "U5") (pin "20") (pinfunction "VCC_20") (pintype "power_in"))
      (node (ref "U5") (pin "4") (pinfunction "VCCIO_4") (pintype "power_in"))
      (node (ref "U6") (pin "5") (pinfunction "IN_5") (pintype "bidirectional"))
      (node (ref "U6") (pin "6") (pinfunction "IN_6") (pintype "bidirectional"))
      (node (ref "USB") (pin "TP") (pinfunction "TP_TP") (pintype "input"))
    )
    (net (code "55") (name "unconnected-(U1-ADC6-Pad19)") (class "Default")
      (node (ref "U1") (pin "19") (pinfunction "ADC6_19") (pintype "input"))
    )
    (net (code "56") (name "unconnected-(U1-ADC7-Pad22)") (class "Default")
      (node (ref "U1") (pin "22") (pinfunction "ADC7_22") (pintype "input"))
    )
    (net (code "57") (name "unconnected-(U1-AREF-Pad20)") (class "Default")
      (node (ref "U1") (pin "20") (pinfunction "AREF_20") (pintype "input"))
    )
    (net (code "58") (name "unconnected-(U1-PC4-Pad27)") (class "Default")
      (node (ref "U1") (pin "27") (pinfunction "PC4_27") (pintype "bidirectional"))
    )
    (net (code "59") (name "unconnected-(U1-PC5-Pad28)") (class "Default")
      (node (ref "U1") (pin "28") (pinfunction "PC5_28") (pintype "bidirectional"))
    )
    (net (code "60") (name "unconnected-(U1-PD6-Pad10)") (class "Default")
      (node (ref "U1") (pin "10") (pinfunction "PD6_10") (pintype "bidirectional"))
    )
    (net (code "61") (name "unconnected-(U1-PD7-Pad11)") (class "Default")
      (node (ref "U1") (pin "11") (pinfunction "PD7_11") (pintype "bidirectional"))
    )
    (net (code "62") (name "unconnected-(U3-EXT_XOSC-Pad32)") (class "Default")
      (node (ref "U3") (pin "32") (pinfunction "EXT_XOSC_32") (pintype "bidirectional"))
    )
    (net (code "63") (name "unconnected-(U3-NC-Pad16)") (class "Default")
      (node (ref "U3") (pin "16") (pinfunction "NC_16") (pintype "bidirectional"))
    )
    (net (code "64") (name "unconnected-(U3-TRX_SW-Pad18)") (class "Default")
      (node (ref "U3") (pin "18") (pinfunction "TRX_SW_18") (pintype "bidirectional"))
    )
    (net (code "65") (name "unconnected-(U5-CBUS0-Pad23)") (class "Default")
      (node (ref "U5") (pin "23") (pinfunction "CBUS0_23") (pintype "bidirectional"))
    )
    (net (code "66") (name "unconnected-(U5-CBUS1-Pad22)") (class "Default")
      (node (ref "U5") (pin "22") (pinfunction "CBUS1_22") (pintype "bidirectional"))
    )
    (net (code "67") (name "unconnected-(U5-CBUS2-Pad13)") (class "Default")
      (node (ref "U5") (pin "13") (pinfunction "CBUS2_13") (pintype "bidirectional"))
    )
    (net (code "68") (name "unconnected-(U5-CBUS3-Pad14)") (class "Default")
      (node (ref "U5") (pin "14") (pinfunction "CBUS3_14") (pintype "bidirectional"))
    )
    (net (code "69") (name "unconnected-(U5-OSCI-Pad27)") (class "Default")
      (node (ref "U5") (pin "27") (pinfunction "OSCI_27") (pintype "input"))
    )
    (net (code "70") (name "unconnected-(U5-OSCO-Pad28)") (class "Default")
      (node (ref "U5") (pin "28") (pinfunction "OSCO_28") (pintype "output"))
    )
    (net (code "71") (name "unconnected-(U5-~{CTS}-Pad11)") (class "Default")
      (node (ref "U5") (pin "11") (pinfunction "~{CTS}_11") (pintype "input"))
    )
    (net (code "72") (name "unconnected-(U5-~{DCD}-Pad10)") (class "Default")
      (node (ref "U5") (pin "10") (pinfunction "~{DCD}_10") (pintype "input"))
    )
    (net (code "73") (name "unconnected-(U5-~{DSR}-Pad9)") (class "Default")
      (node (ref "U5") (pin "9") (pinfunction "~{DSR}_9") (pintype "input"))
    )
    (net (code "74") (name "unconnected-(U5-~{RESET}-Pad19)") (class "Default")
      (node (ref "U5") (pin "19") (pinfunction "~{RESET}_19") (pintype "input"))
    )
    (net (code "75") (name "unconnected-(U5-~{RI}-Pad6)") (class "Default")
      (node (ref "U5") (pin "6") (pinfunction "~{RI}_6") (pintype "input"))
    )
    (net (code "76") (name "unconnected-(U5-~{RTS}-Pad3)") (class "Default")
      (node (ref "U5") (pin "3") (pinfunction "~{RTS}_3") (pintype "output"))
    )
  )
)
